# USB_Power_Distribution.net
KiCad netlist of a schematic drawn in EAGLE
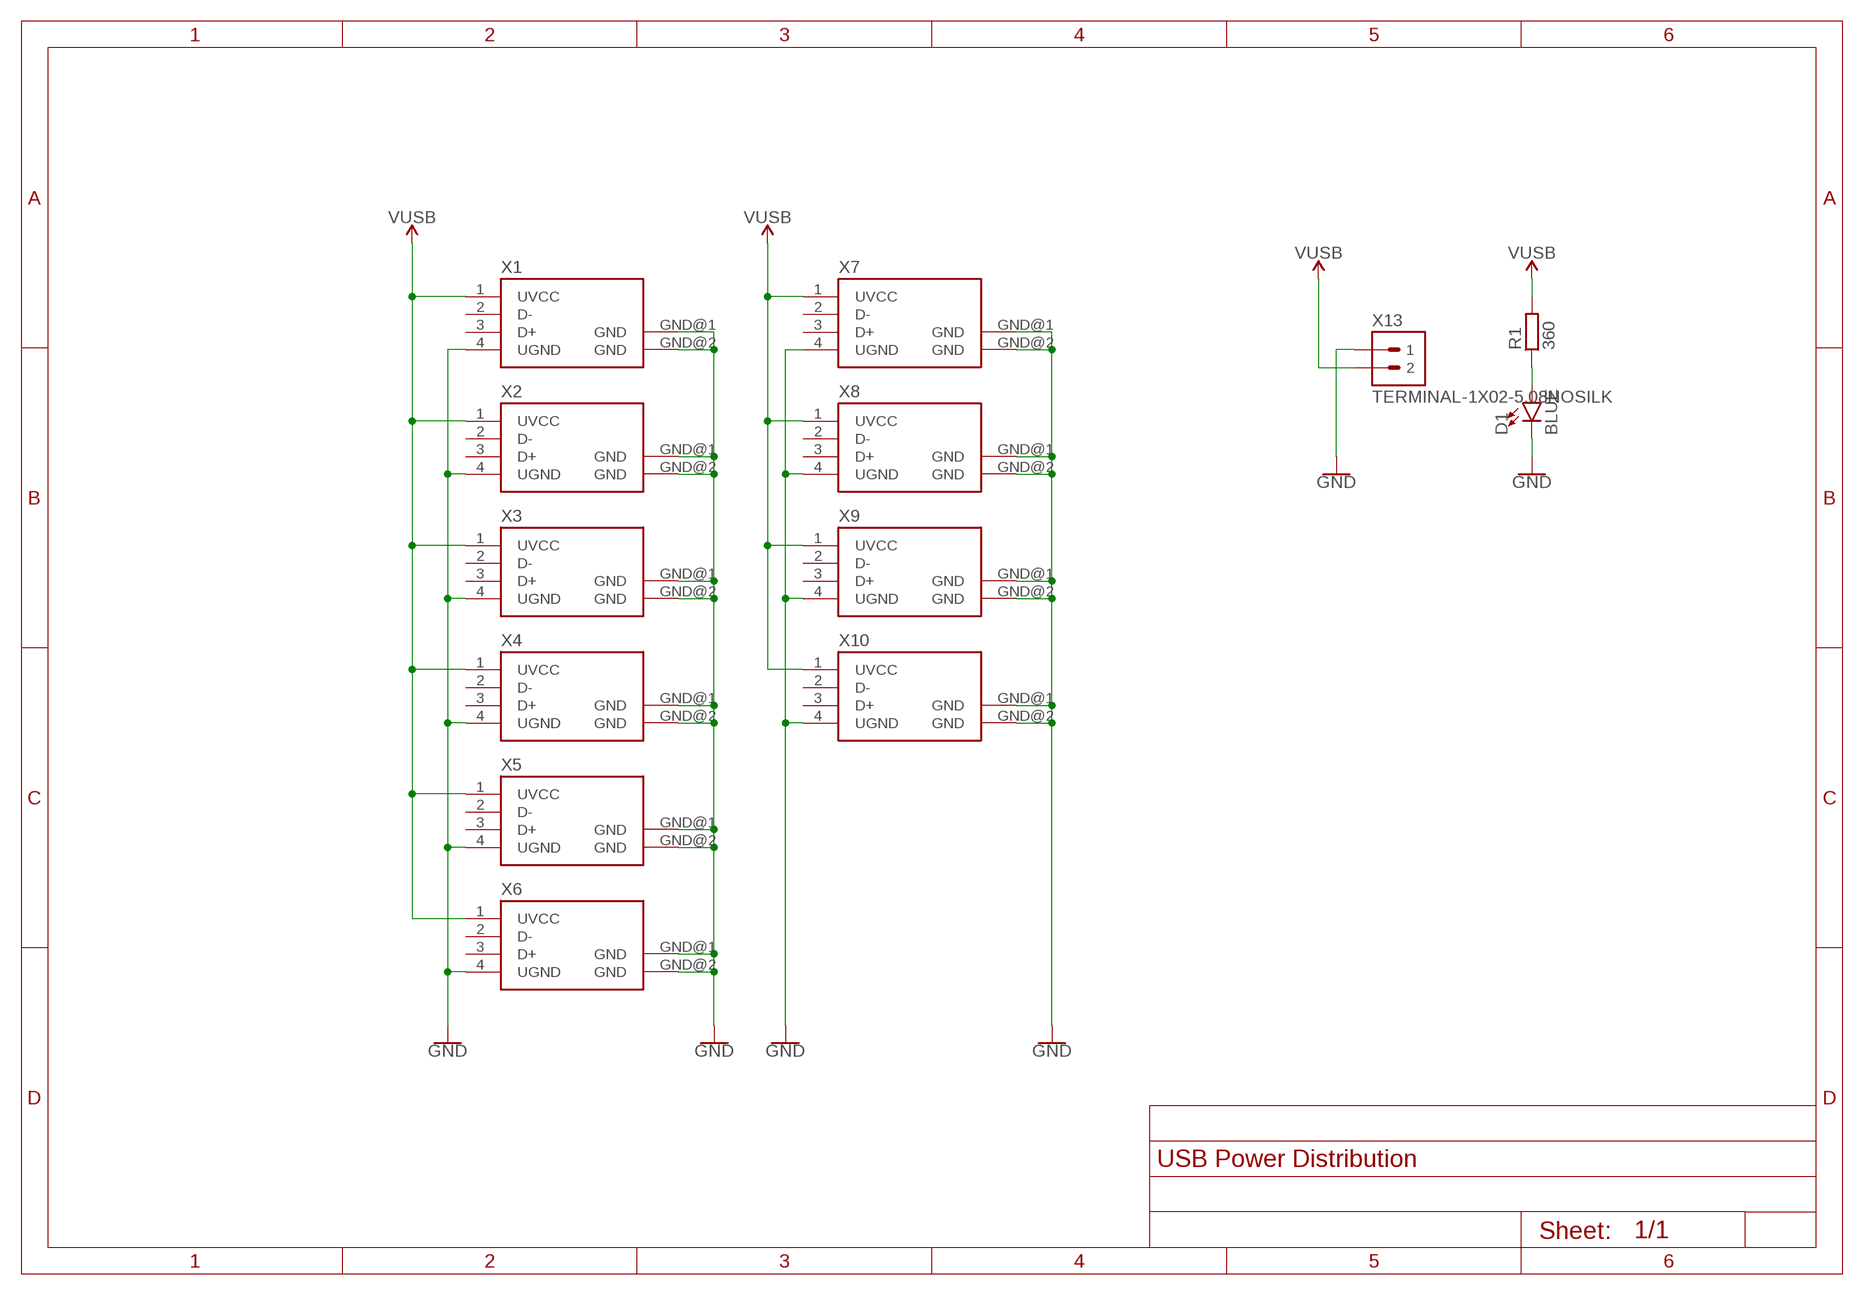
[diagram p0: schematic, sheet 1]

(export (version "E")
  (design (tool "Eeschema 10.0.6"))
  (components
    (comp (ref "D1")
      (value "BLUE")
      (footprint "eagle-import:LED3MM")
      (libsource (lib "eagle-import") (part "LED3MM"))
    )
    (comp (ref "R1")
      (value "360")
      (footprint "eagle-import:R0805")
      (libsource (lib "eagle-import") (part "RESISTOR0805"))
    )
    (comp (ref "X1")
      (value "USB-AVERT-SS-52100-002")
      (footprint "eagle-import:USB-A-VERT-SS-52100-002")
      (libsource (lib "eagle-import") (part "USB-AVERT-SS-52100-002"))
    )
    (comp (ref "X2")
      (value "USB-AVERT-SS-52100-002")
      (footprint "eagle-import:USB-A-VERT-SS-52100-002")
      (libsource (lib "eagle-import") (part "USB-AVERT-SS-52100-002"))
    )
    (comp (ref "X3")
      (value "USB-AVERT-SS-52100-002")
      (footprint "eagle-import:USB-A-VERT-SS-52100-002")
      (libsource (lib "eagle-import") (part "USB-AVERT-SS-52100-002"))
    )
    (comp (ref "X4")
      (value "USB-AVERT-SS-52100-002")
      (footprint "eagle-import:USB-A-VERT-SS-52100-002")
      (libsource (lib "eagle-import") (part "USB-AVERT-SS-52100-002"))
    )
    (comp (ref "X5")
      (value "USB-AVERT-SS-52100-002")
      (footprint "eagle-import:USB-A-VERT-SS-52100-002")
      (libsource (lib "eagle-import") (part "USB-AVERT-SS-52100-002"))
    )
    (comp (ref "X6")
      (value "USB-AVERT-SS-52100-002")
      (footprint "eagle-import:USB-A-VERT-SS-52100-002")
      (libsource (lib "eagle-import") (part "USB-AVERT-SS-52100-002"))
    )
    (comp (ref "X7")
      (value "USB-AVERT-SS-52100-002")
      (footprint "eagle-import:USB-A-VERT-SS-52100-002")
      (libsource (lib "eagle-import") (part "USB-AVERT-SS-52100-002"))
    )
    (comp (ref "X8")
      (value "USB-AVERT-SS-52100-002")
      (footprint "eagle-import:USB-A-VERT-SS-52100-002")
      (libsource (lib "eagle-import") (part "USB-AVERT-SS-52100-002"))
    )
    (comp (ref "X9")
      (value "USB-AVERT-SS-52100-002")
      (footprint "eagle-import:USB-A-VERT-SS-52100-002")
      (libsource (lib "eagle-import") (part "USB-AVERT-SS-52100-002"))
    )
    (comp (ref "X10")
      (value "USB-AVERT-SS-52100-002")
      (footprint "eagle-import:USB-A-VERT-SS-52100-002")
      (libsource (lib "eagle-import") (part "USB-AVERT-SS-52100-002"))
    )
    (comp (ref "X13")
      (value "TERMINAL-1X02-5.08NOSILK")
      (footprint "eagle-import:TERMINAL-5.08-2P-NO-SILK")
      (libsource (lib "eagle-import") (part "TERMINAL-1X02-5.08NOSILK"))
    )
  )
  (nets
    (net (code "1") (name "GND") (class "Default")
      (node (ref "D1") (pin "K") (pinfunction "C_K") (pintype "passive"))
      (node (ref "X1") (pin "4") (pinfunction "UGND_4") (pintype "bidirectional"))
      (node (ref "X1") (pin "GND@1") (pinfunction "GND_GND@1") (pintype "bidirectional"))
      (node (ref "X1") (pin "GND@2") (pinfunction "GND_GND@2") (pintype "bidirectional"))
      (node (ref "X10") (pin "4") (pinfunction "UGND_4") (pintype "bidirectional"))
      (node (ref "X10") (pin "GND@1") (pinfunction "GND_GND@1") (pintype "bidirectional"))
      (node (ref "X10") (pin "GND@2") (pinfunction "GND_GND@2") (pintype "bidirectional"))
      (node (ref "X13") (pin "P$1") (pinfunction "1_P$1") (pintype "passive"))
      (node (ref "X2") (pin "4") (pinfunction "UGND_4") (pintype "bidirectional"))
      (node (ref "X2") (pin "GND@1") (pinfunction "GND_GND@1") (pintype "bidirectional"))
      (node (ref "X2") (pin "GND@2") (pinfunction "GND_GND@2") (pintype "bidirectional"))
      (node (ref "X3") (pin "4") (pinfunction "UGND_4") (pintype "bidirectional"))
      (node (ref "X3") (pin "GND@1") (pinfunction "GND_GND@1") (pintype "bidirectional"))
      (node (ref "X3") (pin "GND@2") (pinfunction "GND_GND@2") (pintype "bidirectional"))
      (node (ref "X4") (pin "4") (pinfunction "UGND_4") (pintype "bidirectional"))
      (node (ref "X4") (pin "GND@1") (pinfunction "GND_GND@1") (pintype "bidirectional"))
      (node (ref "X4") (pin "GND@2") (pinfunction "GND_GND@2") (pintype "bidirectional"))
      (node (ref "X5") (pin "4") (pinfunction "UGND_4") (pintype "bidirectional"))
      (node (ref "X5") (pin "GND@1") (pinfunction "GND_GND@1") (pintype "bidirectional"))
      (node (ref "X5") (pin "GND@2") (pinfunction "GND_GND@2") (pintype "bidirectional"))
      (node (ref "X6") (pin "4") (pinfunction "UGND_4") (pintype "bidirectional"))
      (node (ref "X6") (pin "GND@1") (pinfunction "GND_GND@1") (pintype "bidirectional"))
      (node (ref "X6") (pin "GND@2") (pinfunction "GND_GND@2") (pintype "bidirectional"))
      (node (ref "X7") (pin "4") (pinfunction "UGND_4") (pintype "bidirectional"))
      (node (ref "X7") (pin "GND@1") (pinfunction "GND_GND@1") (pintype "bidirectional"))
      (node (ref "X7") (pin "GND@2") (pinfunction "GND_GND@2") (pintype "bidirectional"))
      (node (ref "X8") (pin "4") (pinfunction "UGND_4") (pintype "bidirectional"))
      (node (ref "X8") (pin "GND@1") (pinfunction "GND_GND@1") (pintype "bidirectional"))
      (node (ref "X8") (pin "GND@2") (pinfunction "GND_GND@2") (pintype "bidirectional"))
      (node (ref "X9") (pin "4") (pinfunction "UGND_4") (pintype "bidirectional"))
      (node (ref "X9") (pin "GND@1") (pinfunction "GND_GND@1") (pintype "bidirectional"))
      (node (ref "X9") (pin "GND@2") (pinfunction "GND_GND@2") (pintype "bidirectional"))
    )
    (net (code "2") (name "Net-(D1-PadA)") (class "Default")
      (node (ref "D1") (pin "A") (pinfunction "A_A") (pintype "passive"))
      (node (ref "R1") (pin "1") (pinfunction "1_1") (pintype "passive"))
    )
    (net (code "3") (name "VUSB") (class "Default")
      (node (ref "R1") (pin "2") (pinfunction "2_2") (pintype "passive"))
      (node (ref "X1") (pin "1") (pinfunction "UVCC_1") (pintype "bidirectional"))
      (node (ref "X10") (pin "1") (pinfunction "UVCC_1") (pintype "bidirectional"))
      (node (ref "X13") (pin "P$2") (pinfunction "2_P$2") (pintype "passive"))
      (node (ref "X2") (pin "1") (pinfunction "UVCC_1") (pintype "bidirectional"))
      (node (ref "X3") (pin "1") (pinfunction "UVCC_1") (pintype "bidirectional"))
      (node (ref "X4") (pin "1") (pinfunction "UVCC_1") (pintype "bidirectional"))
      (node (ref "X5") (pin "1") (pinfunction "UVCC_1") (pintype "bidirectional"))
      (node (ref "X6") (pin "1") (pinfunction "UVCC_1") (pintype "bidirectional"))
      (node (ref "X7") (pin "1") (pinfunction "UVCC_1") (pintype "bidirectional"))
      (node (ref "X8") (pin "1") (pinfunction "UVCC_1") (pintype "bidirectional"))
      (node (ref "X9") (pin "1") (pinfunction "UVCC_1") (pintype "bidirectional"))
    )
    (net (code "4") (name "unconnected-(X1-D+-Pad3)") (class "Default")
      (node (ref "X1") (pin "3") (pinfunction "D+_3") (pintype "bidirectional"))
    )
    (net (code "5") (name "unconnected-(X1-D--Pad2)") (class "Default")
      (node (ref "X1") (pin "2") (pinfunction "D-_2") (pintype "bidirectional"))
    )
    (net (code "6") (name "unconnected-(X2-D+-Pad3)") (class "Default")
      (node (ref "X2") (pin "3") (pinfunction "D+_3") (pintype "bidirectional"))
    )
    (net (code "7") (name "unconnected-(X2-D--Pad2)") (class "Default")
      (node (ref "X2") (pin "2") (pinfunction "D-_2") (pintype "bidirectional"))
    )
    (net (code "8") (name "unconnected-(X3-D+-Pad3)") (class "Default")
      (node (ref "X3") (pin "3") (pinfunction "D+_3") (pintype "bidirectional"))
    )
    (net (code "9") (name "unconnected-(X3-D--Pad2)") (class "Default")
      (node (ref "X3") (pin "2") (pinfunction "D-_2") (pintype "bidirectional"))
    )
    (net (code "10") (name "unconnected-(X4-D+-Pad3)") (class "Default")
      (node (ref "X4") (pin "3") (pinfunction "D+_3") (pintype "bidirectional"))
    )
    (net (code "11") (name "unconnected-(X4-D--Pad2)") (class "Default")
      (node (ref "X4") (pin "2") (pinfunction "D-_2") (pintype "bidirectional"))
    )
    (net (code "12") (name "unconnected-(X5-D+-Pad3)") (class "Default")
      (node (ref "X5") (pin "3") (pinfunction "D+_3") (pintype "bidirectional"))
    )
    (net (code "13") (name "unconnected-(X5-D--Pad2)") (class "Default")
      (node (ref "X5") (pin "2") (pinfunction "D-_2") (pintype "bidirectional"))
    )
    (net (code "14") (name "unconnected-(X6-D+-Pad3)") (class "Default")
      (node (ref "X6") (pin "3") (pinfunction "D+_3") (pintype "bidirectional"))
    )
    (net (code "15") (name "unconnected-(X6-D--Pad2)") (class "Default")
      (node (ref "X6") (pin "2") (pinfunction "D-_2") (pintype "bidirectional"))
    )
    (net (code "16") (name "unconnected-(X7-D+-Pad3)") (class "Default")
      (node (ref "X7") (pin "3") (pinfunction "D+_3") (pintype "bidirectional"))
    )
    (net (code "17") (name "unconnected-(X7-D--Pad2)") (class "Default")
      (node (ref "X7") (pin "2") (pinfunction "D-_2") (pintype "bidirectional"))
    )
    (net (code "18") (name "unconnected-(X8-D+-Pad3)") (class "Default")
      (node (ref "X8") (pin "3") (pinfunction "D+_3") (pintype "bidirectional"))
    )
    (net (code "19") (name "unconnected-(X8-D--Pad2)") (class "Default")
      (node (ref "X8") (pin "2") (pinfunction "D-_2") (pintype "bidirectional"))
    )
    (net (code "20") (name "unconnected-(X9-D+-Pad3)") (class "Default")
      (node (ref "X9") (pin "3") (pinfunction "D+_3") (pintype "bidirectional"))
    )
    (net (code "21") (name "unconnected-(X9-D--Pad2)") (class "Default")
      (node (ref "X9") (pin "2") (pinfunction "D-_2") (pintype "bidirectional"))
    )
    (net (code "22") (name "unconnected-(X10-D+-Pad3)") (class "Default")
      (node (ref "X10") (pin "3") (pinfunction "D+_3") (pintype "bidirectional"))
    )
    (net (code "23") (name "unconnected-(X10-D--Pad2)") (class "Default")
      (node (ref "X10") (pin "2") (pinfunction "D-_2") (pintype "bidirectional"))
    )
  )
)
